# pwm_adapter.net
KiCad netlist of a schematic drawn in EAGLE
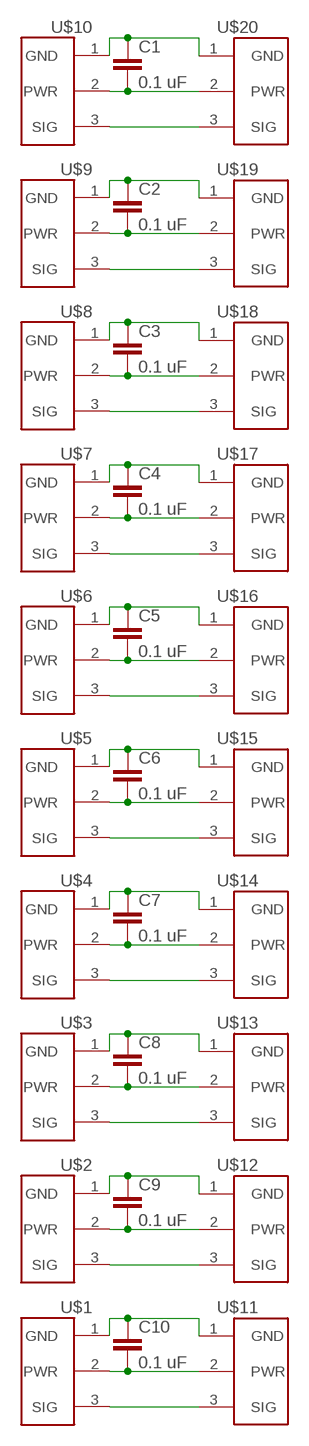
[diagram p0: schematic, sheet 1]

(export (version "E")
  (design (tool "Eeschema 10.0.6"))
  (components
    (comp (ref "C1")
      (value "0.1 uF")
      (footprint "eagle-import:0603")
      (libsource (lib "eagle-import") (part "CAP0603"))
    )
    (comp (ref "C2")
      (value "0.1 uF")
      (footprint "eagle-import:0603")
      (libsource (lib "eagle-import") (part "CAP0603"))
    )
    (comp (ref "C3")
      (value "0.1 uF")
      (footprint "eagle-import:0603")
      (libsource (lib "eagle-import") (part "CAP0603"))
    )
    (comp (ref "C4")
      (value "0.1 uF")
      (footprint "eagle-import:0603")
      (libsource (lib "eagle-import") (part "CAP0603"))
    )
    (comp (ref "C5")
      (value "0.1 uF")
      (footprint "eagle-import:0603")
      (libsource (lib "eagle-import") (part "CAP0603"))
    )
    (comp (ref "C6")
      (value "0.1 uF")
      (footprint "eagle-import:0603")
      (libsource (lib "eagle-import") (part "CAP0603"))
    )
    (comp (ref "C7")
      (value "0.1 uF")
      (footprint "eagle-import:0603")
      (libsource (lib "eagle-import") (part "CAP0603"))
    )
    (comp (ref "C8")
      (value "0.1 uF")
      (footprint "eagle-import:0603")
      (libsource (lib "eagle-import") (part "CAP0603"))
    )
    (comp (ref "C9")
      (value "0.1 uF")
      (footprint "eagle-import:0603")
      (libsource (lib "eagle-import") (part "CAP0603"))
    )
    (comp (ref "C10")
      (value "0.1 uF")
      (footprint "eagle-import:0603")
      (libsource (lib "eagle-import") (part "CAP0603"))
    )
    (comp (ref "U$1")
      (value "22-23-2031GENERIC")
      (footprint "eagle-import:PWM_1X3")
      (libsource (lib "eagle-import") (part "22-23-2031GENERIC"))
    )
    (comp (ref "U$2")
      (value "22-23-2031GENERIC")
      (footprint "eagle-import:PWM_1X3")
      (libsource (lib "eagle-import") (part "22-23-2031GENERIC"))
    )
    (comp (ref "U$3")
      (value "22-23-2031GENERIC")
      (footprint "eagle-import:PWM_1X3")
      (libsource (lib "eagle-import") (part "22-23-2031GENERIC"))
    )
    (comp (ref "U$4")
      (value "22-23-2031GENERIC")
      (footprint "eagle-import:PWM_1X3")
      (libsource (lib "eagle-import") (part "22-23-2031GENERIC"))
    )
    (comp (ref "U$5")
      (value "22-23-2031GENERIC")
      (footprint "eagle-import:PWM_1X3")
      (libsource (lib "eagle-import") (part "22-23-2031GENERIC"))
    )
    (comp (ref "U$6")
      (value "22-23-2031GENERIC")
      (footprint "eagle-import:PWM_1X3")
      (libsource (lib "eagle-import") (part "22-23-2031GENERIC"))
    )
    (comp (ref "U$7")
      (value "22-23-2031GENERIC")
      (footprint "eagle-import:PWM_1X3")
      (libsource (lib "eagle-import") (part "22-23-2031GENERIC"))
    )
    (comp (ref "U$8")
      (value "22-23-2031GENERIC")
      (footprint "eagle-import:PWM_1X3")
      (libsource (lib "eagle-import") (part "22-23-2031GENERIC"))
    )
    (comp (ref "U$9")
      (value "22-23-2031GENERIC")
      (footprint "eagle-import:PWM_1X3")
      (libsource (lib "eagle-import") (part "22-23-2031GENERIC"))
    )
    (comp (ref "U$10")
      (value "22-23-2031GENERIC")
      (footprint "eagle-import:PWM_1X3")
      (libsource (lib "eagle-import") (part "22-23-2031GENERIC"))
    )
    (comp (ref "U$11")
      (value "22-23-2031")
      (footprint "eagle-import:22-23-2031")
      (libsource (lib "eagle-import") (part "22-23-2031"))
    )
    (comp (ref "U$12")
      (value "22-23-2031")
      (footprint "eagle-import:22-23-2031")
      (libsource (lib "eagle-import") (part "22-23-2031"))
    )
    (comp (ref "U$13")
      (value "22-23-2031")
      (footprint "eagle-import:22-23-2031")
      (libsource (lib "eagle-import") (part "22-23-2031"))
    )
    (comp (ref "U$14")
      (value "22-23-2031")
      (footprint "eagle-import:22-23-2031")
      (libsource (lib "eagle-import") (part "22-23-2031"))
    )
    (comp (ref "U$15")
      (value "22-23-2031")
      (footprint "eagle-import:22-23-2031")
      (libsource (lib "eagle-import") (part "22-23-2031"))
    )
    (comp (ref "U$16")
      (value "22-23-2031")
      (footprint "eagle-import:22-23-2031")
      (libsource (lib "eagle-import") (part "22-23-2031"))
    )
    (comp (ref "U$17")
      (value "22-23-2031")
      (footprint "eagle-import:22-23-2031")
      (libsource (lib "eagle-import") (part "22-23-2031"))
    )
    (comp (ref "U$18")
      (value "22-23-2031")
      (footprint "eagle-import:22-23-2031")
      (libsource (lib "eagle-import") (part "22-23-2031"))
    )
    (comp (ref "U$19")
      (value "22-23-2031")
      (footprint "eagle-import:22-23-2031")
      (libsource (lib "eagle-import") (part "22-23-2031"))
    )
    (comp (ref "U$20")
      (value "22-23-2031")
      (footprint "eagle-import:22-23-2031")
      (libsource (lib "eagle-import") (part "22-23-2031"))
    )
  )
  (nets
    (net (code "1") (name "Net-(U$1-GND)") (class "Default")
      (node (ref "C10") (pin "1") (pinfunction "1_1") (pintype "passive"))
      (node (ref "U$1") (pin "1") (pinfunction "GND_1") (pintype "power_in"))
      (node (ref "U$11") (pin "1") (pinfunction "GND_1") (pintype "power_in"))
    )
    (net (code "2") (name "Net-(U$1-PWR)") (class "Default")
      (node (ref "C10") (pin "2") (pinfunction "2_2") (pintype "passive"))
      (node (ref "U$1") (pin "2") (pinfunction "PWR_2") (pintype "power_in"))
      (node (ref "U$11") (pin "2") (pinfunction "PWR_2") (pintype "power_in"))
    )
    (net (code "3") (name "Net-(U$1-SIG)") (class "Default")
      (node (ref "U$1") (pin "3") (pinfunction "SIG_3") (pintype "bidirectional"))
      (node (ref "U$11") (pin "3") (pinfunction "SIG_3") (pintype "bidirectional"))
    )
    (net (code "4") (name "Net-(U$10-GND)") (class "Default")
      (node (ref "C1") (pin "1") (pinfunction "1_1") (pintype "passive"))
      (node (ref "U$10") (pin "1") (pinfunction "GND_1") (pintype "power_in"))
      (node (ref "U$20") (pin "1") (pinfunction "GND_1") (pintype "power_in"))
    )
    (net (code "5") (name "Net-(U$10-PWR)") (class "Default")
      (node (ref "C1") (pin "2") (pinfunction "2_2") (pintype "passive"))
      (node (ref "U$10") (pin "2") (pinfunction "PWR_2") (pintype "power_in"))
      (node (ref "U$20") (pin "2") (pinfunction "PWR_2") (pintype "power_in"))
    )
    (net (code "6") (name "Net-(U$10-SIG)") (class "Default")
      (node (ref "U$10") (pin "3") (pinfunction "SIG_3") (pintype "bidirectional"))
      (node (ref "U$20") (pin "3") (pinfunction "SIG_3") (pintype "bidirectional"))
    )
    (net (code "7") (name "Net-(U$12-GND)") (class "Default")
      (node (ref "C9") (pin "1") (pinfunction "1_1") (pintype "passive"))
      (node (ref "U$12") (pin "1") (pinfunction "GND_1") (pintype "power_in"))
      (node (ref "U$2") (pin "1") (pinfunction "GND_1") (pintype "power_in"))
    )
    (net (code "8") (name "Net-(U$12-PWR)") (class "Default")
      (node (ref "C9") (pin "2") (pinfunction "2_2") (pintype "passive"))
      (node (ref "U$12") (pin "2") (pinfunction "PWR_2") (pintype "power_in"))
      (node (ref "U$2") (pin "2") (pinfunction "PWR_2") (pintype "power_in"))
    )
    (net (code "9") (name "Net-(U$12-SIG)") (class "Default")
      (node (ref "U$12") (pin "3") (pinfunction "SIG_3") (pintype "bidirectional"))
      (node (ref "U$2") (pin "3") (pinfunction "SIG_3") (pintype "bidirectional"))
    )
    (net (code "10") (name "Net-(U$13-GND)") (class "Default")
      (node (ref "C8") (pin "1") (pinfunction "1_1") (pintype "passive"))
      (node (ref "U$13") (pin "1") (pinfunction "GND_1") (pintype "power_in"))
      (node (ref "U$3") (pin "1") (pinfunction "GND_1") (pintype "power_in"))
    )
    (net (code "11") (name "Net-(U$13-PWR)") (class "Default")
      (node (ref "C8") (pin "2") (pinfunction "2_2") (pintype "passive"))
      (node (ref "U$13") (pin "2") (pinfunction "PWR_2") (pintype "power_in"))
      (node (ref "U$3") (pin "2") (pinfunction "PWR_2") (pintype "power_in"))
    )
    (net (code "12") (name "Net-(U$13-SIG)") (class "Default")
      (node (ref "U$13") (pin "3") (pinfunction "SIG_3") (pintype "bidirectional"))
      (node (ref "U$3") (pin "3") (pinfunction "SIG_3") (pintype "bidirectional"))
    )
    (net (code "13") (name "Net-(U$14-GND)") (class "Default")
      (node (ref "C7") (pin "1") (pinfunction "1_1") (pintype "passive"))
      (node (ref "U$14") (pin "1") (pinfunction "GND_1") (pintype "power_in"))
      (node (ref "U$4") (pin "1") (pinfunction "GND_1") (pintype "power_in"))
    )
    (net (code "14") (name "Net-(U$14-PWR)") (class "Default")
      (node (ref "C7") (pin "2") (pinfunction "2_2") (pintype "passive"))
      (node (ref "U$14") (pin "2") (pinfunction "PWR_2") (pintype "power_in"))
      (node (ref "U$4") (pin "2") (pinfunction "PWR_2") (pintype "power_in"))
    )
    (net (code "15") (name "Net-(U$14-SIG)") (class "Default")
      (node (ref "U$14") (pin "3") (pinfunction "SIG_3") (pintype "bidirectional"))
      (node (ref "U$4") (pin "3") (pinfunction "SIG_3") (pintype "bidirectional"))
    )
    (net (code "16") (name "Net-(U$15-GND)") (class "Default")
      (node (ref "C6") (pin "1") (pinfunction "1_1") (pintype "passive"))
      (node (ref "U$15") (pin "1") (pinfunction "GND_1") (pintype "power_in"))
      (node (ref "U$5") (pin "1") (pinfunction "GND_1") (pintype "power_in"))
    )
    (net (code "17") (name "Net-(U$15-PWR)") (class "Default")
      (node (ref "C6") (pin "2") (pinfunction "2_2") (pintype "passive"))
      (node (ref "U$15") (pin "2") (pinfunction "PWR_2") (pintype "power_in"))
      (node (ref "U$5") (pin "2") (pinfunction "PWR_2") (pintype "power_in"))
    )
    (net (code "18") (name "Net-(U$15-SIG)") (class "Default")
      (node (ref "U$15") (pin "3") (pinfunction "SIG_3") (pintype "bidirectional"))
      (node (ref "U$5") (pin "3") (pinfunction "SIG_3") (pintype "bidirectional"))
    )
    (net (code "19") (name "Net-(U$16-GND)") (class "Default")
      (node (ref "C5") (pin "1") (pinfunction "1_1") (pintype "passive"))
      (node (ref "U$16") (pin "1") (pinfunction "GND_1") (pintype "power_in"))
      (node (ref "U$6") (pin "1") (pinfunction "GND_1") (pintype "power_in"))
    )
    (net (code "20") (name "Net-(U$16-PWR)") (class "Default")
      (node (ref "C5") (pin "2") (pinfunction "2_2") (pintype "passive"))
      (node (ref "U$16") (pin "2") (pinfunction "PWR_2") (pintype "power_in"))
      (node (ref "U$6") (pin "2") (pinfunction "PWR_2") (pintype "power_in"))
    )
    (net (code "21") (name "Net-(U$16-SIG)") (class "Default")
      (node (ref "U$16") (pin "3") (pinfunction "SIG_3") (pintype "bidirectional"))
      (node (ref "U$6") (pin "3") (pinfunction "SIG_3") (pintype "bidirectional"))
    )
    (net (code "22") (name "Net-(U$17-GND)") (class "Default")
      (node (ref "C4") (pin "1") (pinfunction "1_1") (pintype "passive"))
      (node (ref "U$17") (pin "1") (pinfunction "GND_1") (pintype "power_in"))
      (node (ref "U$7") (pin "1") (pinfunction "GND_1") (pintype "power_in"))
    )
    (net (code "23") (name "Net-(U$17-PWR)") (class "Default")
      (node (ref "C4") (pin "2") (pinfunction "2_2") (pintype "passive"))
      (node (ref "U$17") (pin "2") (pinfunction "PWR_2") (pintype "power_in"))
      (node (ref "U$7") (pin "2") (pinfunction "PWR_2") (pintype "power_in"))
    )
    (net (code "24") (name "Net-(U$17-SIG)") (class "Default")
      (node (ref "U$17") (pin "3") (pinfunction "SIG_3") (pintype "bidirectional"))
      (node (ref "U$7") (pin "3") (pinfunction "SIG_3") (pintype "bidirectional"))
    )
    (net (code "25") (name "Net-(U$18-GND)") (class "Default")
      (node (ref "C3") (pin "1") (pinfunction "1_1") (pintype "passive"))
      (node (ref "U$18") (pin "1") (pinfunction "GND_1") (pintype "power_in"))
      (node (ref "U$8") (pin "1") (pinfunction "GND_1") (pintype "power_in"))
    )
    (net (code "26") (name "Net-(U$18-PWR)") (class "Default")
      (node (ref "C3") (pin "2") (pinfunction "2_2") (pintype "passive"))
      (node (ref "U$18") (pin "2") (pinfunction "PWR_2") (pintype "power_in"))
      (node (ref "U$8") (pin "2") (pinfunction "PWR_2") (pintype "power_in"))
    )
    (net (code "27") (name "Net-(U$18-SIG)") (class "Default")
      (node (ref "U$18") (pin "3") (pinfunction "SIG_3") (pintype "bidirectional"))
      (node (ref "U$8") (pin "3") (pinfunction "SIG_3") (pintype "bidirectional"))
    )
    (net (code "28") (name "Net-(U$19-GND)") (class "Default")
      (node (ref "C2") (pin "1") (pinfunction "1_1") (pintype "passive"))
      (node (ref "U$19") (pin "1") (pinfunction "GND_1") (pintype "power_in"))
      (node (ref "U$9") (pin "1") (pinfunction "GND_1") (pintype "power_in"))
    )
    (net (code "29") (name "Net-(U$19-PWR)") (class "Default")
      (node (ref "C2") (pin "2") (pinfunction "2_2") (pintype "passive"))
      (node (ref "U$19") (pin "2") (pinfunction "PWR_2") (pintype "power_in"))
      (node (ref "U$9") (pin "2") (pinfunction "PWR_2") (pintype "power_in"))
    )
    (net (code "30") (name "Net-(U$19-SIG)") (class "Default")
      (node (ref "U$19") (pin "3") (pinfunction "SIG_3") (pintype "bidirectional"))
      (node (ref "U$9") (pin "3") (pinfunction "SIG_3") (pintype "bidirectional"))
    )
  )
)
